# MEHCP.net
KiCad netlist of a schematic drawn in Altium Designer
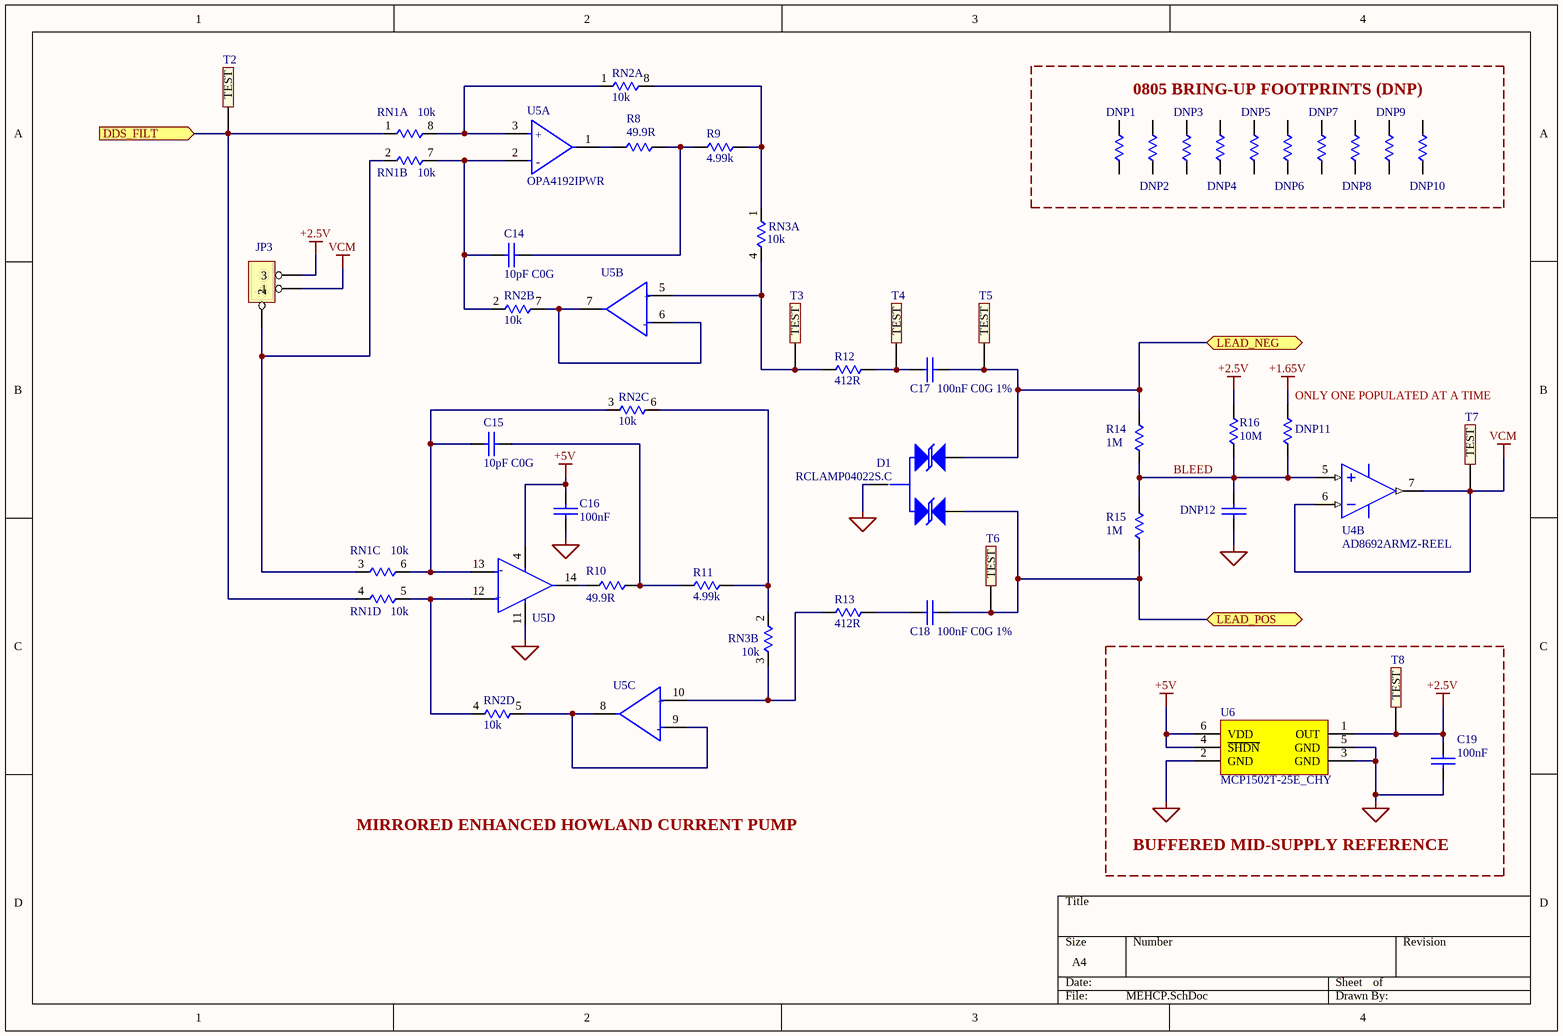
[diagram p0: MEHCP.SchDoc]

(export (version "E")
  (design (tool "Eeschema 10.0.6"))
  (components
    (comp (ref "C14")
      (value "10pF C0G")
      (footprint "0603-CAP")
      (description "CAP CER 10PF 50V C0G 0603")
      (libsource (lib "SGL_Capacitors") (part "Capacitor"))
    )
    (comp (ref "C15")
      (value "10pF C0G")
      (footprint "0603-CAP")
      (description "CAP CER 10PF 50V C0G 0603")
      (libsource (lib "SGL_Capacitors") (part "Capacitor"))
    )
    (comp (ref "C16")
      (value "100nF")
      (footprint "0603-CAP")
      (description "CAP CER 100 NF 50V X7R 0603")
      (libsource (lib "SGL_Capacitors") (part "Capacitor"))
    )
    (comp (ref "C17")
      (value "100nF C0G 1%")
      (footprint "1206-CAP")
      (description "CAP CER 0.1UF 1% 50V C0G/NP0 1206")
      (libsource (lib "SGL_Capacitors") (part "Capacitor"))
    )
    (comp (ref "C18")
      (value "100nF C0G 1%")
      (footprint "1206-CAP")
      (description "CAP CER 0.1UF 1% 50V C0G/NP0 1206")
      (libsource (lib "SGL_Capacitors") (part "Capacitor"))
    )
    (comp (ref "C19")
      (value "100nF")
      (footprint "0603-CAP")
      (description "CAP CER 100 NF 50V X7R 0603")
      (libsource (lib "SGL_Capacitors") (part "Capacitor"))
    )
    (comp (ref "D1")
      (value "RCLAMP04022S.C")
      (footprint "SOT-23 3L")
      (libsource (lib "BioZ") (part "RCLAMP04022S.C"))
    )
    (comp (ref "DNP1")
      (value "240R 0.1%")
      (footprint "0805-RES")
      (description "RES SMD 240 OHM 0.1% 1/8W 0805")
      (libsource (lib "SGL_Resistives") (part "RESISTOR"))
    )
    (comp (ref "DNP2")
      (value "240R 0.1%")
      (footprint "0805-RES")
      (description "RES SMD 240 OHM 0.1% 1/8W 0805")
      (libsource (lib "SGL_Resistives") (part "RESISTOR"))
    )
    (comp (ref "DNP3")
      (value "240R 0.1%")
      (footprint "0805-RES")
      (description "RES SMD 240 OHM 0.1% 1/8W 0805")
      (libsource (lib "SGL_Resistives") (part "RESISTOR"))
    )
    (comp (ref "DNP4")
      (value "240R 0.1%")
      (footprint "0805-RES")
      (description "RES SMD 240 OHM 0.1% 1/8W 0805")
      (libsource (lib "SGL_Resistives") (part "RESISTOR"))
    )
    (comp (ref "DNP5")
      (value "240R 0.1%")
      (footprint "0805-RES")
      (description "RES SMD 240 OHM 0.1% 1/8W 0805")
      (libsource (lib "SGL_Resistives") (part "RESISTOR"))
    )
    (comp (ref "DNP6")
      (value "240R 0.1%")
      (footprint "0805-RES")
      (description "RES SMD 240 OHM 0.1% 1/8W 0805")
      (libsource (lib "SGL_Resistives") (part "RESISTOR"))
    )
    (comp (ref "DNP7")
      (value "240R 0.1%")
      (footprint "0805-RES")
      (description "RES SMD 240 OHM 0.1% 1/8W 0805")
      (libsource (lib "SGL_Resistives") (part "RESISTOR"))
    )
    (comp (ref "DNP8")
      (value "240R 0.1%")
      (footprint "0805-RES")
      (description "RES SMD 240 OHM 0.1% 1/8W 0805")
      (libsource (lib "SGL_Resistives") (part "RESISTOR"))
    )
    (comp (ref "DNP9")
      (value "240R 0.1%")
      (footprint "0805-RES")
      (description "RES SMD 240 OHM 0.1% 1/8W 0805")
      (libsource (lib "SGL_Resistives") (part "RESISTOR"))
    )
    (comp (ref "DNP10")
      (value "240R 0.1%")
      (footprint "0805-RES")
      (description "RES SMD 240 OHM 0.1% 1/8W 0805")
      (libsource (lib "SGL_Resistives") (part "RESISTOR"))
    )
    (comp (ref "DNP11")
      (value "10M")
      (footprint "0603-RES")
      (description "RES SMD 10MOHM 1% 1/10W 0603")
      (libsource (lib "SGL_Resistives") (part "RESISTOR"))
    )
    (comp (ref "DNP12")
      (value "4.7nF C0G")
      (footprint "0603-CAP")
      (description "CAP CER 4700PF 50V C0G 0603")
      (libsource (lib "SGL_Capacitors") (part "Capacitor"))
    )
    (comp (ref "JP3")
      (value "JUMPER1X3")
      (footprint "JUMPER3")
      (description "CONN HEADER VERT 36POS 2.54MM")
      (libsource (lib "SGL_Connectors") (part "JUMPER1X3"))
    )
    (comp (ref "R8")
      (value "49.9R")
      (footprint "0603-RES")
      (description "RES SMD 49.9OHM 0.1% 1/10W 0603")
      (libsource (lib "SGL_Resistives") (part "RESISTOR"))
    )
    (comp (ref "R9")
      (value "4.99k")
      (footprint "0603-RES")
      (description "RES SMD 4.99KOHM 0.1% 1/10W 0603")
      (libsource (lib "SGL_Resistives") (part "RESISTOR"))
    )
    (comp (ref "R10")
      (value "49.9R")
      (footprint "0603-RES")
      (description "RES SMD 49.9OHM 0.1% 1/10W 0603")
      (libsource (lib "SGL_Resistives") (part "RESISTOR"))
    )
    (comp (ref "R11")
      (value "4.99k")
      (footprint "0603-RES")
      (description "RES SMD 4.99KOHM 0.1% 1/10W 0603")
      (libsource (lib "SGL_Resistives") (part "RESISTOR"))
    )
    (comp (ref "R12")
      (value "412R")
      (footprint "0603-RES")
      (description "RES SMD 412OHM 0.1% 1/10W 0603")
      (libsource (lib "SGL_Resistives") (part "RESISTOR"))
    )
    (comp (ref "R13")
      (value "412R")
      (footprint "0603-RES")
      (description "RES SMD 412OHM 0.1% 1/10W 0603")
      (libsource (lib "SGL_Resistives") (part "RESISTOR"))
    )
    (comp (ref "R14")
      (value "1M")
      (footprint "0603-RES")
      (description "RES SMD 1MOHM 0.1% 1/10W 0603")
      (libsource (lib "SGL_Resistives") (part "RESISTOR"))
    )
    (comp (ref "R15")
      (value "1M")
      (footprint "0603-RES")
      (description "RES SMD 1MOHM 0.1% 1/10W 0603")
      (libsource (lib "SGL_Resistives") (part "RESISTOR"))
    )
    (comp (ref "R16")
      (value "10M")
      (footprint "0603-RES")
      (description "RES SMD 10MOHM 1% 1/10W 0603")
      (libsource (lib "SGL_Resistives") (part "RESISTOR"))
    )
    (comp (ref "RN1")
      (value "10k")
      (footprint "1206 4-Resistor Network")
      (description "4 resistor, resistor network in a 8 pin DIP package")
      (libsource (lib "BioZ") (part "ACASA1002S1002P1AT"))
    )
    (comp (ref "RN2")
      (value "10k")
      (footprint "1206 4-Resistor Network")
      (description "4 resistor, resistor network in a 8 pin DIP package")
      (libsource (lib "BioZ") (part "ACASA1002S1002P1AT"))
    )
    (comp (ref "RN3")
      (value "10k")
      (footprint "0606 2-RESISTOR NETWORK")
      (description "2 resistor, resistor network, 10k/10k 0.1% abs. and 0.05% rel., 0606, 25ppm")
      (libsource (lib "BioZ") (part "ACASN1002S1002P1AT"))
    )
    (comp (ref "T2")
      (value "5002K")
      (footprint "TESTPOINT White")
      (description "PC TEST POINT MINIATURE WHITE")
      (libsource (lib "SGL_Connectors") (part "Testpoint white"))
    )
    (comp (ref "T3")
      (value "5002K")
      (footprint "TESTPOINT White")
      (description "PC TEST POINT MINIATURE WHITE")
      (libsource (lib "SGL_Connectors") (part "Testpoint white"))
    )
    (comp (ref "T4")
      (value "5002K")
      (footprint "TESTPOINT White")
      (description "PC TEST POINT MINIATURE WHITE")
      (libsource (lib "SGL_Connectors") (part "Testpoint white"))
    )
    (comp (ref "T5")
      (value "5002K")
      (footprint "TESTPOINT White")
      (description "PC TEST POINT MINIATURE WHITE")
      (libsource (lib "SGL_Connectors") (part "Testpoint white"))
    )
    (comp (ref "T6")
      (value "5002K")
      (footprint "TESTPOINT White")
      (description "PC TEST POINT MINIATURE WHITE")
      (libsource (lib "SGL_Connectors") (part "Testpoint white"))
    )
    (comp (ref "T7")
      (value "5002K")
      (footprint "TESTPOINT White")
      (description "PC TEST POINT MINIATURE WHITE")
      (libsource (lib "SGL_Connectors") (part "Testpoint white"))
    )
    (comp (ref "T8")
      (value "5002K")
      (footprint "TESTPOINT White")
      (description "PC TEST POINT MINIATURE WHITE")
      (libsource (lib "SGL_Connectors") (part "Testpoint white"))
    )
    (comp (ref "U4")
      (value "AD8692ARMZ-REEL")
      (footprint "ADI-RM-8_M")
      (fields (field (name "MANUFACTURER") "Analog Devices") (field (name "GENERIC PART NUMBER") "AD8692"))
      (libsource (lib "Altium Content Vault") (part "ADI-ADA4000-2-X-8"))
    )
    (comp (ref "U5")
      (value "OPA4192IPWR")
      (footprint "FP-PW0014A-IPC_C")
      (description "IC OPAMP GP 4 CIRCUIT 14TSSOP")
      (libsource (lib "") (part "CMP-04895-000439-1_1"))
    )
    (comp (ref "U6")
      (value "MCP1502T-25E_CHY")
      (footprint "SOT95P280X145-6N")
      (description "Series Voltage Reference IC Fixed 2.5V V +/-0.1% 20 mA SOT-23-6")
      (fields
        (field (name "MOUSER PART NUMBER") "579-MCP1502T-25E/CHY")
        (field (name "MANUFACTURER_PART_NUMBER") "MCP1502T-25E/CHY")
      )
      (libsource (lib "BioZ") (part "MCP1502T-25E_CHY"))
    )
  )
  (nets
    (net (code "1") (name "+1.65V") (class "Default")
      (node (ref "DNP11") (pin "2") (pinfunction "2_2") (pintype "passive"))
    )
    (net (code "2") (name "+2.5V") (class "Default")
      (node (ref "C19") (pin "1") (pinfunction "1_1") (pintype "passive"))
      (node (ref "JP3") (pin "3") (pinfunction "3_3") (pintype "passive"))
      (node (ref "R16") (pin "2") (pinfunction "2_2") (pintype "passive"))
      (node (ref "T8") (pin "1") (pinfunction "TEST_1") (pintype "passive"))
      (node (ref "U6") (pin "1") (pinfunction "OUT_1") (pintype "passive"))
    )
    (net (code "3") (name "+5V") (class "Default")
      (node (ref "C16") (pin "1") (pinfunction "1_1") (pintype "passive"))
      (node (ref "U5") (pin "4") (pinfunction "V+_4") (pintype "power_in"))
      (node (ref "U6") (pin "4") (pinfunction "~{SHDN}_4") (pintype "passive"))
      (node (ref "U6") (pin "6") (pinfunction "VDD_6") (pintype "passive"))
    )
    (net (code "4") (name "/BLEED") (class "Default")
      (node (ref "DNP11") (pin "1") (pinfunction "1_1") (pintype "passive"))
      (node (ref "DNP12") (pin "2") (pinfunction "2_2") (pintype "passive"))
      (node (ref "R14") (pin "1") (pinfunction "1_1") (pintype "passive"))
      (node (ref "R15") (pin "2") (pinfunction "2_2") (pintype "passive"))
      (node (ref "R16") (pin "1") (pinfunction "1_1") (pintype "passive"))
      (node (ref "U4") (pin "5") (pinfunction "+IN_B_5") (pintype "input"))
    )
    (net (code "5") (name "/DDS_FILT") (class "Default")
      (node (ref "RN1") (pin "1") (pinfunction "1_1") (pintype "passive"))
      (node (ref "RN1") (pin "4") (pinfunction "4_4") (pintype "passive"))
      (node (ref "T2") (pin "1") (pinfunction "TEST_1") (pintype "passive"))
    )
    (net (code "6") (name "/LEAD_NEG") (class "Default")
      (node (ref "C17") (pin "2") (pinfunction "2_2") (pintype "passive"))
      (node (ref "D1") (pin "2") (pinfunction "2_2") (pintype "passive"))
      (node (ref "R14") (pin "2") (pinfunction "2_2") (pintype "passive"))
      (node (ref "T5") (pin "1") (pinfunction "TEST_1") (pintype "passive"))
    )
    (net (code "7") (name "/LEAD_POS") (class "Default")
      (node (ref "C18") (pin "2") (pinfunction "2_2") (pintype "passive"))
      (node (ref "D1") (pin "1") (pinfunction "1_1") (pintype "passive"))
      (node (ref "R15") (pin "1") (pinfunction "1_1") (pintype "passive"))
      (node (ref "T6") (pin "1") (pinfunction "TEST_1") (pintype "passive"))
    )
    (net (code "8") (name "GND") (class "Default")
      (node (ref "C16") (pin "2") (pinfunction "2_2") (pintype "passive"))
      (node (ref "C19") (pin "2") (pinfunction "2_2") (pintype "passive"))
      (node (ref "D1") (pin "3") (pinfunction "3_3") (pintype "passive"))
      (node (ref "DNP12") (pin "1") (pinfunction "1_1") (pintype "passive"))
      (node (ref "U5") (pin "11") (pinfunction "V-_11") (pintype "power_in"))
      (node (ref "U6") (pin "2") (pinfunction "GND_2") (pintype "passive"))
      (node (ref "U6") (pin "3") (pinfunction "GND_3") (pintype "passive"))
      (node (ref "U6") (pin "5") (pinfunction "GND_5") (pintype "passive"))
    )
    (net (code "9") (name "Net-(C14-Pad2)") (class "Default")
      (node (ref "C14") (pin "2") (pinfunction "2_2") (pintype "passive"))
      (node (ref "R8") (pin "2") (pinfunction "2_2") (pintype "passive"))
      (node (ref "R9") (pin "1") (pinfunction "1_1") (pintype "passive"))
    )
    (net (code "10") (name "Net-(C15-Pad2)") (class "Default")
      (node (ref "C15") (pin "2") (pinfunction "2_2") (pintype "passive"))
      (node (ref "R10") (pin "2") (pinfunction "2_2") (pintype "passive"))
      (node (ref "R11") (pin "1") (pinfunction "1_1") (pintype "passive"))
    )
    (net (code "11") (name "Net-(C18-Pad1)") (class "Default")
      (node (ref "C18") (pin "1") (pinfunction "1_1") (pintype "passive"))
      (node (ref "R13") (pin "2") (pinfunction "2_2") (pintype "passive"))
    )
    (net (code "12") (name "Net-(JP3-Pad2)") (class "Default")
      (node (ref "JP3") (pin "2") (pinfunction "2_2") (pintype "passive"))
      (node (ref "RN1") (pin "2") (pinfunction "2_2") (pintype "passive"))
      (node (ref "RN1") (pin "3") (pinfunction "3_3") (pintype "passive"))
    )
    (net (code "13") (name "Net-(R9-Pad2)") (class "Default")
      (node (ref "R9") (pin "2") (pinfunction "2_2") (pintype "passive"))
      (node (ref "RN2") (pin "8") (pinfunction "8_8") (pintype "passive"))
      (node (ref "RN3") (pin "1") (pinfunction "1_1") (pintype "passive"))
    )
    (net (code "14") (name "Net-(R11-Pad2)") (class "Default")
      (node (ref "R11") (pin "2") (pinfunction "2_2") (pintype "passive"))
      (node (ref "RN2") (pin "6") (pinfunction "6_6") (pintype "passive"))
      (node (ref "RN3") (pin "2") (pinfunction "2_2") (pintype "passive"))
    )
    (net (code "15") (name "Net-(T3-TEST)") (class "Default")
      (node (ref "R12") (pin "1") (pinfunction "1_1") (pintype "passive"))
      (node (ref "RN3") (pin "4") (pinfunction "4_4") (pintype "passive"))
      (node (ref "T3") (pin "1") (pinfunction "TEST_1") (pintype "passive"))
      (node (ref "U5") (pin "5") (pinfunction "+IN_B_5") (pintype "tri_state"))
    )
    (net (code "16") (name "Net-(T4-TEST)") (class "Default")
      (node (ref "C17") (pin "1") (pinfunction "1_1") (pintype "passive"))
      (node (ref "R12") (pin "2") (pinfunction "2_2") (pintype "passive"))
      (node (ref "T4") (pin "1") (pinfunction "TEST_1") (pintype "passive"))
    )
    (net (code "17") (name "Net-(U5A-+IN_A)") (class "Default")
      (node (ref "RN1") (pin "8") (pinfunction "8_8") (pintype "passive"))
      (node (ref "RN2") (pin "1") (pinfunction "1_1") (pintype "passive"))
      (node (ref "U5") (pin "3") (pinfunction "+IN_A_3") (pintype "tri_state"))
    )
    (net (code "18") (name "Net-(U5A--IN_A)") (class "Default")
      (node (ref "C14") (pin "1") (pinfunction "1_1") (pintype "passive"))
      (node (ref "RN1") (pin "7") (pinfunction "7_7") (pintype "passive"))
      (node (ref "RN2") (pin "2") (pinfunction "2_2") (pintype "passive"))
      (node (ref "U5") (pin "2") (pinfunction "-IN_A_2") (pintype "tri_state"))
    )
    (net (code "19") (name "Net-(U5A-OUT_A)") (class "Default")
      (node (ref "R8") (pin "1") (pinfunction "1_1") (pintype "passive"))
      (node (ref "U5") (pin "1") (pinfunction "OUT_A_1") (pintype "passive"))
    )
    (net (code "20") (name "Net-(U5B--IN_A)") (class "Default")
      (node (ref "RN2") (pin "7") (pinfunction "7_7") (pintype "passive"))
      (node (ref "U5") (pin "6") (pinfunction "-IN_A_6") (pintype "tri_state"))
      (node (ref "U5") (pin "7") (pinfunction "OUT_B_7") (pintype "passive"))
    )
    (net (code "21") (name "Net-(U5C-+IN_C)") (class "Default")
      (node (ref "R13") (pin "1") (pinfunction "1_1") (pintype "passive"))
      (node (ref "RN3") (pin "3") (pinfunction "3_3") (pintype "passive"))
      (node (ref "U5") (pin "10") (pinfunction "+IN_C_10") (pintype "tri_state"))
    )
    (net (code "22") (name "Net-(U5C--IN_C)") (class "Default")
      (node (ref "RN2") (pin "5") (pinfunction "5_5") (pintype "passive"))
      (node (ref "U5") (pin "8") (pinfunction "OUT_C_8") (pintype "passive"))
      (node (ref "U5") (pin "9") (pinfunction "-IN_C_9") (pintype "tri_state"))
    )
    (net (code "23") (name "Net-(U5D-+IN_D)") (class "Default")
      (node (ref "RN1") (pin "5") (pinfunction "5_5") (pintype "passive"))
      (node (ref "RN2") (pin "4") (pinfunction "4_4") (pintype "passive"))
      (node (ref "U5") (pin "12") (pinfunction "+IN_D_12") (pintype "tri_state"))
    )
    (net (code "24") (name "Net-(U5D--IN_D)") (class "Default")
      (node (ref "C15") (pin "1") (pinfunction "1_1") (pintype "passive"))
      (node (ref "RN1") (pin "6") (pinfunction "6_6") (pintype "passive"))
      (node (ref "RN2") (pin "3") (pinfunction "3_3") (pintype "passive"))
      (node (ref "U5") (pin "13") (pinfunction "-IN_D_13") (pintype "tri_state"))
    )
    (net (code "25") (name "Net-(U5D-OUT_D)") (class "Default")
      (node (ref "R10") (pin "1") (pinfunction "1_1") (pintype "passive"))
      (node (ref "U5") (pin "14") (pinfunction "OUT_D_14") (pintype "passive"))
    )
    (net (code "26") (name "VCM") (class "Default")
      (node (ref "JP3") (pin "1") (pinfunction "1_1") (pintype "passive"))
      (node (ref "T7") (pin "1") (pinfunction "TEST_1") (pintype "passive"))
      (node (ref "U4") (pin "6") (pinfunction "-IN_B_6") (pintype "input"))
      (node (ref "U4") (pin "7") (pinfunction "OUT_B_7") (pintype "output"))
    )
    (net (code "27") (name "unconnected-(DNP1-Pad1)") (class "Default")
      (node (ref "DNP1") (pin "1") (pinfunction "1_1") (pintype "passive"))
    )
    (net (code "28") (name "unconnected-(DNP1-Pad2)") (class "Default")
      (node (ref "DNP1") (pin "2") (pinfunction "2_2") (pintype "passive"))
    )
    (net (code "29") (name "unconnected-(DNP2-Pad1)") (class "Default")
      (node (ref "DNP2") (pin "1") (pinfunction "1_1") (pintype "passive"))
    )
    (net (code "30") (name "unconnected-(DNP2-Pad2)") (class "Default")
      (node (ref "DNP2") (pin "2") (pinfunction "2_2") (pintype "passive"))
    )
    (net (code "31") (name "unconnected-(DNP3-Pad1)") (class "Default")
      (node (ref "DNP3") (pin "1") (pinfunction "1_1") (pintype "passive"))
    )
    (net (code "32") (name "unconnected-(DNP3-Pad2)") (class "Default")
      (node (ref "DNP3") (pin "2") (pinfunction "2_2") (pintype "passive"))
    )
    (net (code "33") (name "unconnected-(DNP4-Pad1)") (class "Default")
      (node (ref "DNP4") (pin "1") (pinfunction "1_1") (pintype "passive"))
    )
    (net (code "34") (name "unconnected-(DNP4-Pad2)") (class "Default")
      (node (ref "DNP4") (pin "2") (pinfunction "2_2") (pintype "passive"))
    )
    (net (code "35") (name "unconnected-(DNP5-Pad1)") (class "Default")
      (node (ref "DNP5") (pin "1") (pinfunction "1_1") (pintype "passive"))
    )
    (net (code "36") (name "unconnected-(DNP5-Pad2)") (class "Default")
      (node (ref "DNP5") (pin "2") (pinfunction "2_2") (pintype "passive"))
    )
    (net (code "37") (name "unconnected-(DNP6-Pad1)") (class "Default")
      (node (ref "DNP6") (pin "1") (pinfunction "1_1") (pintype "passive"))
    )
    (net (code "38") (name "unconnected-(DNP6-Pad2)") (class "Default")
      (node (ref "DNP6") (pin "2") (pinfunction "2_2") (pintype "passive"))
    )
    (net (code "39") (name "unconnected-(DNP7-Pad1)") (class "Default")
      (node (ref "DNP7") (pin "1") (pinfunction "1_1") (pintype "passive"))
    )
    (net (code "40") (name "unconnected-(DNP7-Pad2)") (class "Default")
      (node (ref "DNP7") (pin "2") (pinfunction "2_2") (pintype "passive"))
    )
    (net (code "41") (name "unconnected-(DNP8-Pad1)") (class "Default")
      (node (ref "DNP8") (pin "1") (pinfunction "1_1") (pintype "passive"))
    )
    (net (code "42") (name "unconnected-(DNP8-Pad2)") (class "Default")
      (node (ref "DNP8") (pin "2") (pinfunction "2_2") (pintype "passive"))
    )
    (net (code "43") (name "unconnected-(DNP9-Pad1)") (class "Default")
      (node (ref "DNP9") (pin "1") (pinfunction "1_1") (pintype "passive"))
    )
    (net (code "44") (name "unconnected-(DNP9-Pad2)") (class "Default")
      (node (ref "DNP9") (pin "2") (pinfunction "2_2") (pintype "passive"))
    )
    (net (code "45") (name "unconnected-(DNP10-Pad1)") (class "Default")
      (node (ref "DNP10") (pin "1") (pinfunction "1_1") (pintype "passive"))
    )
    (net (code "46") (name "unconnected-(DNP10-Pad2)") (class "Default")
      (node (ref "DNP10") (pin "2") (pinfunction "2_2") (pintype "passive"))
    )
  )
)
